# DSO_ADC.net
KiCad netlist of a schematic drawn in Altium Designer
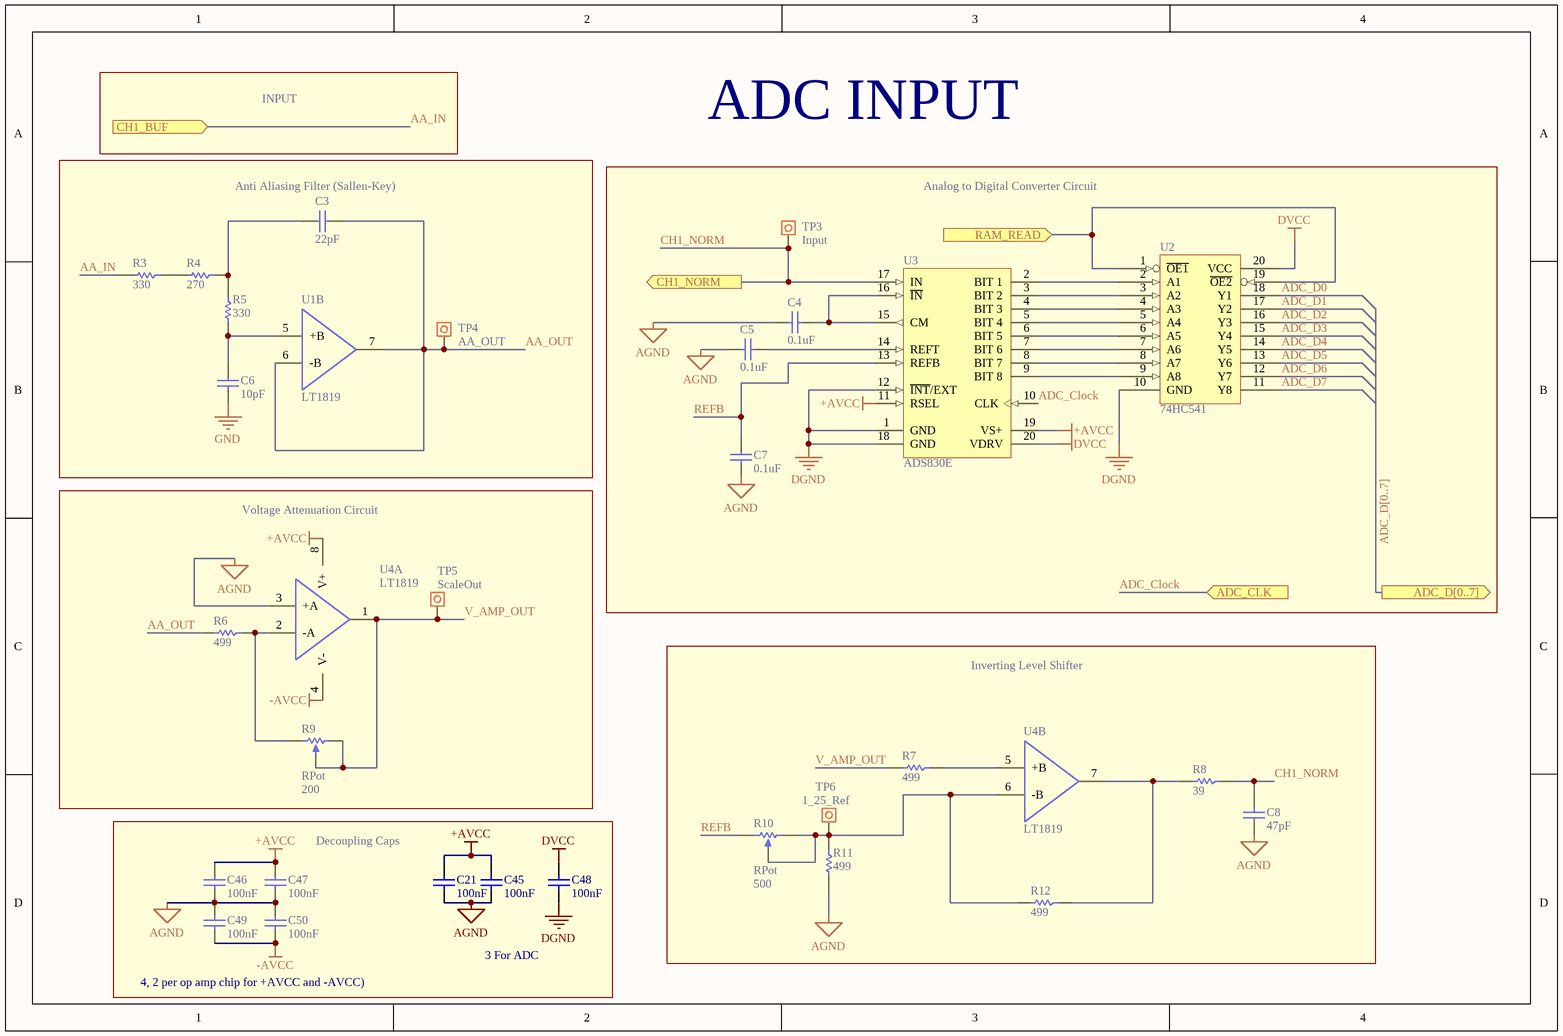
[diagram p0: DSO_ADC.SchDoc]

(export (version "E")
  (design (tool "Eeschema 10.0.6"))
  (components
    (comp (ref "C3")
      (value "22pF")
      (footprint "0805C")
      (description "Capacitor")
      (fields (field (name "REVIEWED BY") "RM - 2018/08/05"))
      (libsource (lib "DSO") (part "C"))
    )
    (comp (ref "C4")
      (value "0.1uF")
      (footprint "0805C")
      (description "Capacitor")
      (fields (field (name "REVIEWED BY") "RM - 2018/08/05"))
      (libsource (lib "DSO") (part "C"))
    )
    (comp (ref "C5")
      (value "0.1uF")
      (footprint "0805C")
      (description "Capacitor")
      (fields (field (name "REVIEWED BY") "RM - 2018/08/05"))
      (libsource (lib "DSO") (part "C"))
    )
    (comp (ref "C6")
      (value "10pF")
      (footprint "0805C")
      (description "Capacitor")
      (fields (field (name "REVIEWED BY") "RM - 2018/08/05"))
      (libsource (lib "DSO") (part "C"))
    )
    (comp (ref "C7")
      (value "0.1uF")
      (footprint "0805C")
      (description "Capacitor")
      (fields (field (name "REVIEWED BY") "RM - 2018/08/05"))
      (libsource (lib "DSO") (part "C"))
    )
    (comp (ref "C8")
      (value "47pF")
      (footprint "0805C")
      (description "Capacitor")
      (fields (field (name "REVIEWED BY") "RM - 2018/08/05"))
      (libsource (lib "DSO") (part "C"))
    )
    (comp (ref "C21")
      (value "100nF")
      (footprint "0805C")
      (description "Capacitor")
      (fields (field (name "REVIEWED BY") "RM - 2018/08/05"))
      (libsource (lib "DSO") (part "C"))
    )
    (comp (ref "C45")
      (value "100nF")
      (footprint "0805C")
      (description "Capacitor")
      (fields (field (name "REVIEWED BY") "RM - 2018/08/05"))
      (libsource (lib "DSO") (part "C"))
    )
    (comp (ref "C46")
      (value "100nF")
      (footprint "0805C")
      (description "Capacitor")
      (fields (field (name "REVIEWED BY") "RM - 2018/08/05"))
      (libsource (lib "DSO") (part "C"))
    )
    (comp (ref "C47")
      (value "100nF")
      (footprint "0805C")
      (description "Capacitor")
      (fields (field (name "REVIEWED BY") "RM - 2018/08/05"))
      (libsource (lib "DSO") (part "C"))
    )
    (comp (ref "C48")
      (value "100nF")
      (footprint "0805C")
      (description "Capacitor")
      (fields (field (name "REVIEWED BY") "RM - 2018/08/05"))
      (libsource (lib "DSO") (part "C"))
    )
    (comp (ref "C49")
      (value "100nF")
      (footprint "0805C")
      (description "Capacitor")
      (fields (field (name "REVIEWED BY") "RM - 2018/08/05"))
      (libsource (lib "DSO") (part "C"))
    )
    (comp (ref "C50")
      (value "100nF")
      (footprint "0805C")
      (description "Capacitor")
      (fields (field (name "REVIEWED BY") "RM - 2018/08/05"))
      (libsource (lib "DSO") (part "C"))
    )
    (comp (ref "R3")
      (value "330")
      (footprint "0805")
      (description "Resistor")
      (fields (field (name "REVIEWED BY") "RM - 2018/08/05"))
      (libsource (lib "DSO") (part "R"))
    )
    (comp (ref "R4")
      (value "270")
      (footprint "0805")
      (description "Resistor")
      (fields (field (name "REVIEWED BY") "RM - 2018/08/05"))
      (libsource (lib "DSO") (part "R"))
    )
    (comp (ref "R5")
      (value "330")
      (footprint "0805")
      (description "Resistor")
      (fields (field (name "REVIEWED BY") "RM - 2018/08/05"))
      (libsource (lib "DSO") (part "R"))
    )
    (comp (ref "R6")
      (value "499")
      (footprint "0805")
      (description "Resistor")
      (fields (field (name "REVIEWED BY") "RM - 2018/08/05"))
      (libsource (lib "DSO") (part "R"))
    )
    (comp (ref "R7")
      (value "499")
      (footprint "0805")
      (description "Resistor")
      (fields (field (name "REVIEWED BY") "RM - 2018/08/05"))
      (libsource (lib "DSO") (part "R"))
    )
    (comp (ref "R8")
      (value "39")
      (footprint "0805")
      (description "Resistor")
      (fields (field (name "REVIEWED BY") "RM - 2018/08/05"))
      (libsource (lib "DSO") (part "R"))
    )
    (comp (ref "R9")
      (value "RPot")
      (footprint "VR5")
      (description "Potentiometer")
      (fields (field (name "ALTIUM_VALUE") "200") (field (name "PUBLISHER") "Altium Limited"))
      (libsource (lib "DSO") (part "RPot"))
    )
    (comp (ref "R10")
      (value "RPot")
      (footprint "VR5")
      (description "Potentiometer")
      (fields (field (name "ALTIUM_VALUE") "500") (field (name "PUBLISHER") "Altium Limited"))
      (libsource (lib "DSO") (part "RPot"))
    )
    (comp (ref "R11")
      (value "499")
      (footprint "0805")
      (description "Resistor")
      (fields (field (name "REVIEWED BY") "RM - 2018/08/05"))
      (libsource (lib "DSO") (part "R"))
    )
    (comp (ref "R12")
      (value "499")
      (footprint "0805")
      (description "Resistor")
      (fields (field (name "REVIEWED BY") "RM - 2018/08/05"))
      (libsource (lib "DSO") (part "R"))
    )
    (comp (ref "TP3")
      (value "Input")
      (footprint "Testpoin")
      (description "Pad")
      (fields (field (name "Comment") "INPUT"))
      (libsource (lib "DSO") (part "Test Point"))
    )
    (comp (ref "TP4")
      (value "AA_OUT")
      (footprint "Testpoin")
      (description "Pad")
      (fields (field (name "Comment") "INPUT"))
      (libsource (lib "DSO") (part "Test Point"))
    )
    (comp (ref "TP5")
      (value "ScaleOut")
      (footprint "Testpoin")
      (description "Pad")
      (fields (field (name "Comment") "INPUT"))
      (libsource (lib "DSO") (part "Test Point"))
    )
    (comp (ref "TP6")
      (value "1_25_Ref")
      (footprint "Testpoin")
      (description "Pad")
      (fields (field (name "Comment") "INPUT"))
      (libsource (lib "DSO") (part "Test Point"))
    )
    (comp (ref "U1")
      (value "LT1819")
      (footprint "SOIC-8")
      (description "OpAmp High Frequency Dual")
      (fields (field (name "REVIEWED BY") "RM - 2018/08/05"))
      (libsource (lib "DSO") (part "LT1819"))
    )
    (comp (ref "U2")
      (value "74HC541")
      (footprint "SOT163-1_N")
      (description "(ADV) Octal Buffer, Line Driver")
      (fields (field (name "REVIEWED BY") "RM - 2018/08/05"))
      (libsource (lib "DSO") (part "74HC541"))
    )
    (comp (ref "U3")
      (value "ADS830E")
      (footprint "TI-DBQ20_L")
      (fields (field (name "REVIEWED BY") "RM - 2018/08/05"))
      (libsource (lib "DSO") (part "ADS830E"))
    )
    (comp (ref "U4")
      (value "LT1819")
      (footprint "SOIC-8")
      (description "OpAmp High Frequency Dual")
      (fields (field (name "REVIEWED BY") "RM - 2018/08/05"))
      (libsource (lib "DSO") (part "LT1819"))
    )
  )
  (nets
    (net (code "1") (name "+AVCC") (class "Default")
      (node (ref "C21") (pin "1") (pinfunction "1_1") (pintype "passive"))
      (node (ref "C45") (pin "1") (pinfunction "1_1") (pintype "passive"))
      (node (ref "C46") (pin "1") (pinfunction "1_1") (pintype "passive"))
      (node (ref "C47") (pin "1") (pinfunction "1_1") (pintype "passive"))
      (node (ref "U3") (pin "11") (pinfunction "RSEL_11") (pintype "input"))
      (node (ref "U3") (pin "19") (pinfunction "VS+_19") (pintype "power_in"))
      (node (ref "U4") (pin "8") (pinfunction "V+_8") (pintype "passive"))
    )
    (net (code "2") (name "-AVCC") (class "Default")
      (node (ref "C49") (pin "1") (pinfunction "1_1") (pintype "passive"))
      (node (ref "C50") (pin "1") (pinfunction "1_1") (pintype "passive"))
      (node (ref "U4") (pin "4") (pinfunction "V-_4") (pintype "passive"))
    )
    (net (code "3") (name "/AA_IN") (class "Default") (node (ref "R3") (pin "2") (pintype "passive")))
    (net (code "4") (name "/AA_OUT") (class "Default")
      (node (ref "C3") (pin "1") (pinfunction "1_1") (pintype "passive"))
      (node (ref "R6") (pin "2") (pintype "passive"))
      (node (ref "TP4") (pin "1") (pintype "passive"))
      (node (ref "U1") (pin "6") (pinfunction "-B_6") (pintype "passive"))
      (node (ref "U1") (pin "7") (pinfunction "OUTB_7") (pintype "passive"))
    )
    (net (code "5") (name "/ADC_Clock") (class "Default")
      (node (ref "U3") (pin "10") (pinfunction "CLK_10") (pintype "input"))
    )
    (net (code "6") (name "/ADC_D0") (class "Default")
      (node (ref "U2") (pin "18") (pinfunction "Y1_18") (pintype "tri_state"))
    )
    (net (code "7") (name "/ADC_D1") (class "Default")
      (node (ref "U2") (pin "17") (pinfunction "Y2_17") (pintype "tri_state"))
    )
    (net (code "8") (name "/ADC_D2") (class "Default")
      (node (ref "U2") (pin "16") (pinfunction "Y3_16") (pintype "tri_state"))
    )
    (net (code "9") (name "/ADC_D3") (class "Default")
      (node (ref "U2") (pin "15") (pinfunction "Y4_15") (pintype "tri_state"))
    )
    (net (code "10") (name "/ADC_D4") (class "Default")
      (node (ref "U2") (pin "14") (pinfunction "Y5_14") (pintype "tri_state"))
    )
    (net (code "11") (name "/ADC_D5") (class "Default")
      (node (ref "U2") (pin "13") (pinfunction "Y6_13") (pintype "tri_state"))
    )
    (net (code "12") (name "/ADC_D6") (class "Default")
      (node (ref "U2") (pin "12") (pinfunction "Y7_12") (pintype "tri_state"))
    )
    (net (code "13") (name "/ADC_D7") (class "Default")
      (node (ref "U2") (pin "11") (pinfunction "Y8_11") (pintype "tri_state"))
    )
    (net (code "15") (name "/CH1_NORM") (class "Default")
      (node (ref "C8") (pin "1") (pinfunction "1_1") (pintype "passive"))
      (node (ref "R8") (pin "1") (pintype "passive"))
      (node (ref "TP3") (pin "1") (pintype "passive"))
      (node (ref "U3") (pin "17") (pinfunction "IN_17") (pintype "input"))
    )
    (net (code "16") (name "/RAM_READ") (class "Default")
      (node (ref "U2") (pin "1") (pinfunction "~{OE1}_1") (pintype "input"))
      (node (ref "U2") (pin "19") (pinfunction "~{OE2}_19") (pintype "input"))
    )
    (net (code "17") (name "/REFB") (class "Default")
      (node (ref "C7") (pin "2") (pinfunction "2_2") (pintype "passive"))
      (node (ref "R10") (pin "1") (pinfunction "TOP_1") (pintype "passive"))
      (node (ref "U3") (pin "13") (pinfunction "REFB_13") (pintype "input"))
    )
    (net (code "18") (name "/V_AMP_OUT") (class "Default")
      (node (ref "R7") (pin "2") (pintype "passive"))
      (node (ref "R9") (pin "2") (pinfunction "TAP_2") (pintype "passive"))
      (node (ref "R9") (pin "3") (pinfunction "BOT_3") (pintype "passive"))
      (node (ref "TP5") (pin "1") (pintype "passive"))
      (node (ref "U4") (pin "1") (pinfunction "OUTA_1") (pintype "passive"))
    )
    (net (code "19") (name "AGND") (class "Default")
      (node (ref "C21") (pin "2") (pinfunction "2_2") (pintype "passive"))
      (node (ref "C4") (pin "1") (pinfunction "1_1") (pintype "passive"))
      (node (ref "C45") (pin "2") (pinfunction "2_2") (pintype "passive"))
      (node (ref "C46") (pin "2") (pinfunction "2_2") (pintype "passive"))
      (node (ref "C47") (pin "2") (pinfunction "2_2") (pintype "passive"))
      (node (ref "C49") (pin "2") (pinfunction "2_2") (pintype "passive"))
      (node (ref "C5") (pin "1") (pinfunction "1_1") (pintype "passive"))
      (node (ref "C50") (pin "2") (pinfunction "2_2") (pintype "passive"))
      (node (ref "C7") (pin "1") (pinfunction "1_1") (pintype "passive"))
      (node (ref "C8") (pin "2") (pinfunction "2_2") (pintype "passive"))
      (node (ref "R11") (pin "2") (pintype "passive"))
      (node (ref "U4") (pin "3") (pinfunction "+A_3") (pintype "passive"))
    )
    (net (code "20") (name "DGND") (class "Default")
      (node (ref "C48") (pin "2") (pinfunction "2_2") (pintype "passive"))
      (node (ref "U2") (pin "10") (pinfunction "GND_10") (pintype "power_in"))
      (node (ref "U3") (pin "1") (pinfunction "GND_1") (pintype "power_in"))
      (node (ref "U3") (pin "12") (pinfunction "~{INT}/EXT_12") (pintype "input"))
      (node (ref "U3") (pin "18") (pinfunction "GND_18") (pintype "power_in"))
    )
    (net (code "21") (name "DVCC") (class "Default")
      (node (ref "C48") (pin "1") (pinfunction "1_1") (pintype "passive"))
      (node (ref "U2") (pin "20") (pinfunction "VCC_20") (pintype "power_in"))
      (node (ref "U3") (pin "20") (pinfunction "VDRV_20") (pintype "power_in"))
    )
    (net (code "22") (name "GND") (class "Default")
      (node (ref "C6") (pin "2") (pinfunction "2_2") (pintype "passive"))
    )
    (net (code "23") (name "Net-(C3-Pad2)") (class "Default")
      (node (ref "C3") (pin "2") (pinfunction "2_2") (pintype "passive"))
      (node (ref "R4") (pin "1") (pintype "passive"))
      (node (ref "R5") (pin "1") (pintype "passive"))
    )
    (net (code "24") (name "Net-(R3-Pad1)") (class "Default")
      (node (ref "R3") (pin "1") (pintype "passive"))
      (node (ref "R4") (pin "2") (pintype "passive"))
    )
    (net (code "25") (name "Net-(R9-TOP)") (class "Default")
      (node (ref "R6") (pin "1") (pintype "passive"))
      (node (ref "R9") (pin "1") (pinfunction "TOP_1") (pintype "passive"))
      (node (ref "U4") (pin "2") (pinfunction "-A_2") (pintype "passive"))
    )
    (net (code "26") (name "Net-(R10-BOT)") (class "Default")
      (node (ref "R10") (pin "2") (pinfunction "TAP_2") (pintype "passive"))
      (node (ref "R10") (pin "3") (pinfunction "BOT_3") (pintype "passive"))
      (node (ref "R11") (pin "1") (pintype "passive"))
      (node (ref "R12") (pin "2") (pintype "passive"))
      (node (ref "TP6") (pin "1") (pintype "passive"))
      (node (ref "U4") (pin "6") (pinfunction "-B_6") (pintype "passive"))
    )
    (net (code "27") (name "Net-(U1B-+B)") (class "Default")
      (node (ref "C6") (pin "1") (pinfunction "1_1") (pintype "passive"))
      (node (ref "R5") (pin "2") (pintype "passive"))
      (node (ref "U1") (pin "5") (pinfunction "+B_5") (pintype "passive"))
    )
    (net (code "28") (name "Net-(U2-A1)") (class "Default")
      (node (ref "U2") (pin "2") (pinfunction "A1_2") (pintype "input"))
      (node (ref "U3") (pin "2") (pinfunction "BIT_1_2") (pintype "tri_state"))
    )
    (net (code "29") (name "Net-(U2-A2)") (class "Default")
      (node (ref "U2") (pin "3") (pinfunction "A2_3") (pintype "input"))
      (node (ref "U3") (pin "3") (pinfunction "BIT_2_3") (pintype "tri_state"))
    )
    (net (code "30") (name "Net-(U2-A3)") (class "Default")
      (node (ref "U2") (pin "4") (pinfunction "A3_4") (pintype "input"))
      (node (ref "U3") (pin "4") (pinfunction "BIT_3_4") (pintype "tri_state"))
    )
    (net (code "31") (name "Net-(U2-A4)") (class "Default")
      (node (ref "U2") (pin "5") (pinfunction "A4_5") (pintype "input"))
      (node (ref "U3") (pin "5") (pinfunction "BIT_4_5") (pintype "tri_state"))
    )
    (net (code "32") (name "Net-(U2-A5)") (class "Default")
      (node (ref "U2") (pin "6") (pinfunction "A5_6") (pintype "input"))
      (node (ref "U3") (pin "6") (pinfunction "BIT_5_6") (pintype "tri_state"))
    )
    (net (code "33") (name "Net-(U2-A6)") (class "Default")
      (node (ref "U2") (pin "7") (pinfunction "A6_7") (pintype "input"))
      (node (ref "U3") (pin "7") (pinfunction "BIT_6_7") (pintype "tri_state"))
    )
    (net (code "34") (name "Net-(U2-A7)") (class "Default")
      (node (ref "U2") (pin "8") (pinfunction "A7_8") (pintype "input"))
      (node (ref "U3") (pin "8") (pinfunction "BIT_7_8") (pintype "tri_state"))
    )
    (net (code "35") (name "Net-(U2-A8)") (class "Default")
      (node (ref "U2") (pin "9") (pinfunction "A8_9") (pintype "input"))
      (node (ref "U3") (pin "9") (pinfunction "BIT_8_9") (pintype "tri_state"))
    )
    (net (code "36") (name "Net-(U3-CM)") (class "Default")
      (node (ref "C4") (pin "2") (pinfunction "2_2") (pintype "passive"))
      (node (ref "U3") (pin "15") (pinfunction "CM_15") (pintype "output"))
      (node (ref "U3") (pin "16") (pinfunction "~{IN}_16") (pintype "input"))
    )
    (net (code "37") (name "Net-(U3-REFT)") (class "Default")
      (node (ref "C5") (pin "2") (pinfunction "2_2") (pintype "passive"))
      (node (ref "U3") (pin "14") (pinfunction "REFT_14") (pintype "input"))
    )
    (net (code "38") (name "Net-(U4B-+B)") (class "Default")
      (node (ref "R7") (pin "1") (pintype "passive"))
      (node (ref "U4") (pin "5") (pinfunction "+B_5") (pintype "passive"))
    )
    (net (code "39") (name "Net-(U4B-OUTB)") (class "Default")
      (node (ref "R12") (pin "1") (pintype "passive"))
      (node (ref "R8") (pin "2") (pintype "passive"))
      (node (ref "U4") (pin "7") (pinfunction "OUTB_7") (pintype "passive"))
    )
  )
)
